# Control_Board_V2.net
KiCad netlist of a schematic drawn in EAGLE
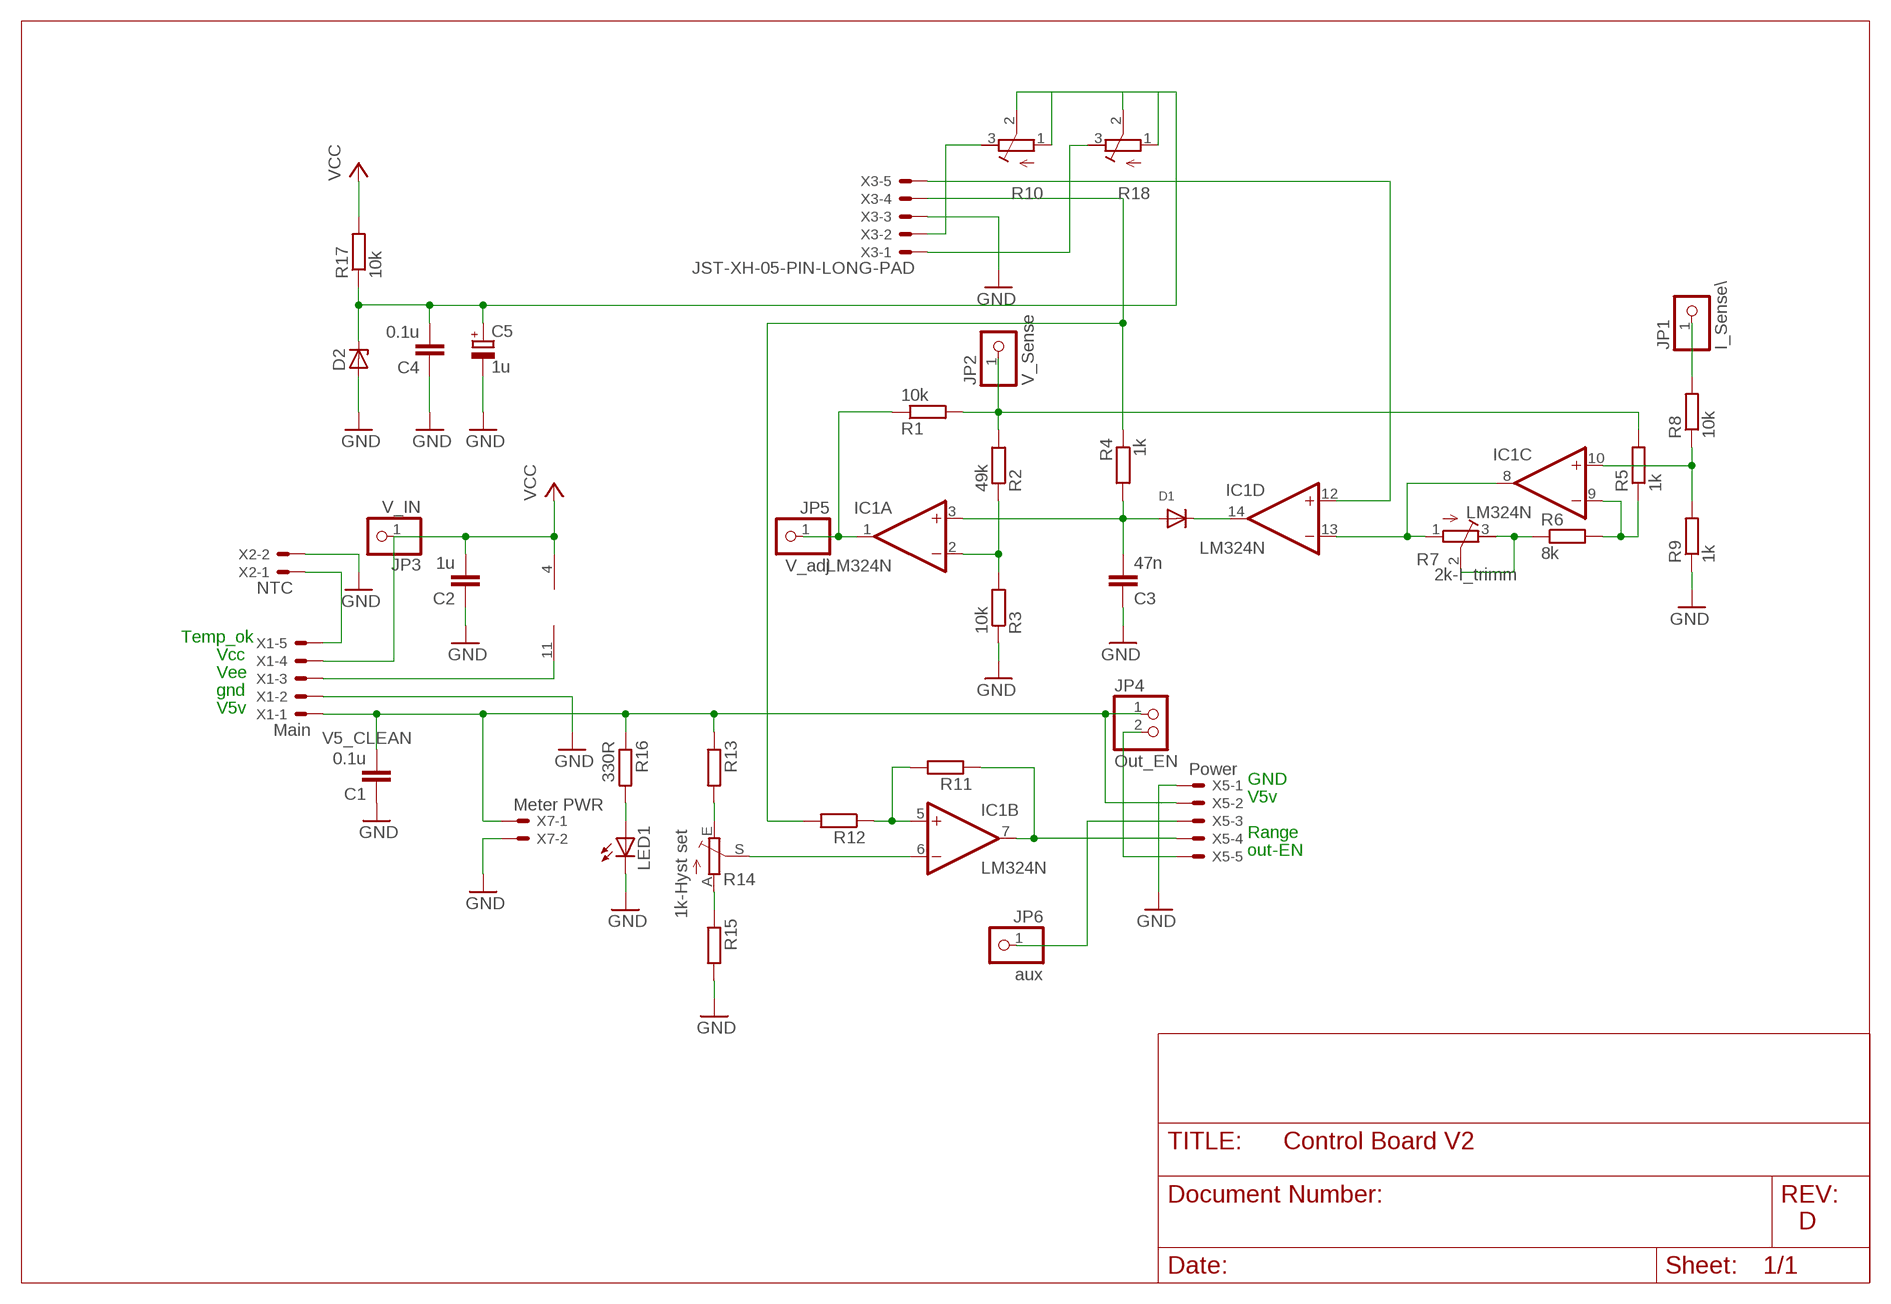
[diagram p0: schematic, sheet 1]

(export (version "E")
  (design (tool "Eeschema 10.0.6"))
  (components
    (comp (ref "C1")
      (value "0.1u")
      (footprint "eagle-import:C050-025X075")
      (libsource (lib "eagle-import") (part "C-EU050-025X075"))
    )
    (comp (ref "C2")
      (value "1u")
      (footprint "eagle-import:C050-025X075")
      (libsource (lib "eagle-import") (part "C-EU050-025X075"))
    )
    (comp (ref "C3")
      (value "47n")
      (footprint "eagle-import:C050-025X075")
      (libsource (lib "eagle-import") (part "C-EU050-025X075"))
    )
    (comp (ref "C4")
      (value "0.1u")
      (footprint "eagle-import:C050-025X075")
      (libsource (lib "eagle-import") (part "C-EU050-025X075"))
    )
    (comp (ref "C5")
      (value "1u")
      (footprint "eagle-import:E5-10,5")
      (libsource (lib "eagle-import") (part "CPOL-EUE5-10.5"))
    )
    (comp (ref "D1")
      (value "DIODEDO-1N4148")
      (footprint "eagle-import:DO-1N4148")
      (libsource (lib "eagle-import") (part "DIODEDO-1N4148"))
    )
    (comp (ref "D2")
      (value "ZENER-DIODEDO35Z10")
      (footprint "eagle-import:DO35Z10")
      (libsource (lib "eagle-import") (part "ZENER-DIODEDO35Z10"))
    )
    (comp (ref "IC1")
      (value "LM324N")
      (footprint "eagle-import:DIL14")
      (libsource (lib "eagle-import") (part "LM324N"))
    )
    (comp (ref "JP1")
      (value "I_Sense\\")
      (footprint "eagle-import:1X01")
      (libsource (lib "eagle-import") (part "PINHD-1X1"))
    )
    (comp (ref "JP2")
      (value "V_Sense")
      (footprint "eagle-import:1X01")
      (libsource (lib "eagle-import") (part "PINHD-1X1"))
    )
    (comp (ref "JP3")
      (value "V_IN")
      (footprint "eagle-import:1X01")
      (libsource (lib "eagle-import") (part "PINHD-1X1"))
    )
    (comp (ref "JP4")
      (value "Out_EN")
      (footprint "eagle-import:1X02")
      (libsource (lib "eagle-import") (part "PINHD-1X2"))
    )
    (comp (ref "JP5")
      (value "V_adj")
      (footprint "eagle-import:1X01")
      (libsource (lib "eagle-import") (part "PINHD-1X1"))
    )
    (comp (ref "JP6")
      (value "aux")
      (footprint "eagle-import:1X01")
      (libsource (lib "eagle-import") (part "PINHD-1X1"))
    )
    (comp (ref "LED1")
      (value "LED3MM")
      (footprint "eagle-import:LED3MM")
      (libsource (lib "eagle-import") (part "LED3MM"))
    )
    (comp (ref "R1")
      (value "10k")
      (footprint "eagle-import:0204_7")
      (libsource (lib "eagle-import") (part "R-EU_0204/7"))
    )
    (comp (ref "R2")
      (value "49k")
      (footprint "eagle-import:0204_7")
      (libsource (lib "eagle-import") (part "R-EU_0204/7"))
    )
    (comp (ref "R3")
      (value "10k")
      (footprint "eagle-import:0204_7")
      (libsource (lib "eagle-import") (part "R-EU_0204/7"))
    )
    (comp (ref "R4")
      (value "1k")
      (footprint "eagle-import:0204_7")
      (libsource (lib "eagle-import") (part "R-EU_0204/7"))
    )
    (comp (ref "R5")
      (value "1k")
      (footprint "eagle-import:0204_5")
      (libsource (lib "eagle-import") (part "R-EU_0204/5"))
    )
    (comp (ref "R6")
      (value "8k")
      (footprint "eagle-import:0204V")
      (libsource (lib "eagle-import") (part "R-EU_0204/2V"))
    )
    (comp (ref "R7")
      (value "2k-I_trimm")
      (footprint "eagle-import:RTRIM64W")
      (libsource (lib "eagle-import") (part "R-TRIMM64W"))
    )
    (comp (ref "R8")
      (value "10k")
      (footprint "eagle-import:0204_7")
      (libsource (lib "eagle-import") (part "R-EU_0204/7"))
    )
    (comp (ref "R9")
      (value "1k")
      (footprint "eagle-import:0204_7")
      (libsource (lib "eagle-import") (part "R-EU_0204/7"))
    )
    (comp (ref "R10")
      (value "R-TRIMM64W")
      (footprint "eagle-import:RTRIM64W")
      (libsource (lib "eagle-import") (part "R-TRIMM64W"))
    )
    (comp (ref "R11")
      (value "R-EU_0204/5")
      (footprint "eagle-import:0204_5")
      (libsource (lib "eagle-import") (part "R-EU_0204/5"))
    )
    (comp (ref "R12")
      (value "R-EU_0204/2V")
      (footprint "eagle-import:0204V")
      (libsource (lib "eagle-import") (part "R-EU_0204/2V"))
    )
    (comp (ref "R13")
      (value "R-EU_0204/2V")
      (footprint "eagle-import:0204V")
      (libsource (lib "eagle-import") (part "R-EU_0204/2V"))
    )
    (comp (ref "R14")
      (value "1k-Hyst set")
      (footprint "eagle-import:B25P")
      (libsource (lib "eagle-import") (part "TRIM_EU-B25P"))
    )
    (comp (ref "R15")
      (value "R-EU_0204/7")
      (footprint "eagle-import:0204_7")
      (libsource (lib "eagle-import") (part "R-EU_0204/7"))
    )
    (comp (ref "R16")
      (value "330R")
      (footprint "eagle-import:0207_2V")
      (libsource (lib "eagle-import") (part "resistor_R-EU_0207/2V"))
    )
    (comp (ref "R17")
      (value "10k")
      (footprint "eagle-import:0204_7")
      (libsource (lib "eagle-import") (part "R-EU_0204/7"))
    )
    (comp (ref "R18")
      (value "R-TRIMM64W")
      (footprint "eagle-import:RTRIM64W")
      (libsource (lib "eagle-import") (part "R-TRIMM64W"))
    )
    (comp (ref "X1")
      (value "Main")
      (footprint "eagle-import:JST-XH-05-PACKAGE-LONG-PAD")
      (libsource (lib "eagle-import") (part "JST-XH-05-PIN-LONG-PAD"))
    )
    (comp (ref "X2")
      (value "NTC")
      (footprint "eagle-import:JST-XH-02-PACKAGE-LONG-PAD")
      (libsource (lib "eagle-import") (part "JST-XH-02-PIN-LONG-PAD"))
    )
    (comp (ref "X3")
      (value "JST-XH-05-PIN-LONG-PAD")
      (footprint "eagle-import:JST-XH-05-PACKAGE-LONG-PAD")
      (libsource (lib "eagle-import") (part "JST-XH-05-PIN-LONG-PAD"))
    )
    (comp (ref "X5")
      (value "Power")
      (footprint "eagle-import:JST-XH-05-PACKAGE-LONG-PAD")
      (libsource (lib "eagle-import") (part "JST-XH-05-PIN-LONG-PAD"))
    )
    (comp (ref "X7")
      (value "Meter PWR")
      (footprint "eagle-import:JST-XH-02-PACKAGE-LONG-PAD")
      (libsource (lib "eagle-import") (part "JST-XH-02-PIN-LONG-PAD"))
    )
  )
  (nets
    (net (code "1") (name "/V5_CLEAN") (class "Default")
      (node (ref "C1") (pin "2") (pinfunction "2_2") (pintype "passive"))
      (node (ref "JP4") (pin "1") (pinfunction "1_1") (pintype "passive"))
      (node (ref "R13") (pin "1") (pinfunction "1_1") (pintype "passive"))
      (node (ref "R16") (pin "1") (pinfunction "1_1") (pintype "passive"))
      (node (ref "X1") (pin "1") (pinfunction "S_1") (pintype "passive"))
      (node (ref "X5") (pin "2") (pinfunction "S_2") (pintype "passive"))
      (node (ref "X7") (pin "1") (pinfunction "S_1") (pintype "passive"))
    )
    (net (code "2") (name "GND") (class "Default")
      (node (ref "C1") (pin "1") (pinfunction "1_1") (pintype "passive"))
      (node (ref "C2") (pin "1") (pinfunction "1_1") (pintype "passive"))
      (node (ref "C3") (pin "1") (pinfunction "1_1") (pintype "passive"))
      (node (ref "C4") (pin "1") (pinfunction "1_1") (pintype "passive"))
      (node (ref "C5") (pin "-") (pinfunction "-_-") (pintype "passive"))
      (node (ref "D2") (pin "A") (pinfunction "A_A") (pintype "passive"))
      (node (ref "LED1") (pin "K") (pinfunction "C_K") (pintype "passive"))
      (node (ref "R15") (pin "2") (pinfunction "2_2") (pintype "passive"))
      (node (ref "R3") (pin "1") (pinfunction "1_1") (pintype "passive"))
      (node (ref "R9") (pin "1") (pinfunction "1_1") (pintype "passive"))
      (node (ref "X1") (pin "2") (pinfunction "S_2") (pintype "passive"))
      (node (ref "X2") (pin "2") (pinfunction "S_2") (pintype "passive"))
      (node (ref "X3") (pin "3") (pinfunction "S_3") (pintype "passive"))
      (node (ref "X5") (pin "1") (pinfunction "S_1") (pintype "passive"))
      (node (ref "X7") (pin "2") (pinfunction "S_2") (pintype "passive"))
    )
    (net (code "3") (name "Net-(IC1A-+IN)") (class "Default")
      (node (ref "C3") (pin "2") (pinfunction "2_2") (pintype "passive"))
      (node (ref "D1") (pin "A") (pinfunction "A_A") (pintype "passive"))
      (node (ref "IC1") (pin "3") (pinfunction "+IN_3") (pintype "input"))
      (node (ref "R4") (pin "2") (pinfunction "2_2") (pintype "passive"))
    )
    (net (code "4") (name "Net-(IC1A--IN)") (class "Default")
      (node (ref "IC1") (pin "2") (pinfunction "-IN_2") (pintype "input"))
      (node (ref "R2") (pin "1") (pinfunction "1_1") (pintype "passive"))
      (node (ref "R3") (pin "2") (pinfunction "2_2") (pintype "passive"))
    )
    (net (code "5") (name "Net-(IC1A-OUT)") (class "Default")
      (node (ref "IC1") (pin "1") (pinfunction "OUT_1") (pintype "output"))
      (node (ref "JP5") (pin "1") (pinfunction "1_1") (pintype "passive"))
      (node (ref "R1") (pin "1") (pinfunction "1_1") (pintype "passive"))
    )
    (net (code "6") (name "Net-(IC1B-+IN)") (class "Default")
      (node (ref "IC1") (pin "5") (pinfunction "+IN_5") (pintype "input"))
      (node (ref "R11") (pin "2") (pinfunction "2_2") (pintype "passive"))
      (node (ref "R12") (pin "1") (pinfunction "1_1") (pintype "passive"))
    )
    (net (code "7") (name "Net-(IC1B--IN)") (class "Default")
      (node (ref "IC1") (pin "6") (pinfunction "-IN_6") (pintype "input"))
      (node (ref "R14") (pin "S") (pinfunction "S_S") (pintype "passive"))
    )
    (net (code "8") (name "Net-(IC1B-OUT)") (class "Default")
      (node (ref "IC1") (pin "7") (pinfunction "OUT_7") (pintype "output"))
      (node (ref "R11") (pin "1") (pinfunction "1_1") (pintype "passive"))
      (node (ref "X5") (pin "4") (pinfunction "S_4") (pintype "passive"))
    )
    (net (code "9") (name "Net-(IC1C-+IN)") (class "Default")
      (node (ref "IC1") (pin "10") (pinfunction "+IN_10") (pintype "input"))
      (node (ref "R8") (pin "1") (pinfunction "1_1") (pintype "passive"))
      (node (ref "R9") (pin "2") (pinfunction "2_2") (pintype "passive"))
    )
    (net (code "10") (name "Net-(IC1C--IN)") (class "Default")
      (node (ref "IC1") (pin "9") (pinfunction "-IN_9") (pintype "input"))
      (node (ref "R5") (pin "1") (pinfunction "1_1") (pintype "passive"))
      (node (ref "R6") (pin "2") (pinfunction "2_2") (pintype "passive"))
    )
    (net (code "11") (name "Net-(IC1C-OUT)") (class "Default")
      (node (ref "IC1") (pin "13") (pinfunction "-IN_13") (pintype "input"))
      (node (ref "IC1") (pin "8") (pinfunction "OUT_8") (pintype "output"))
      (node (ref "R7") (pin "1") (pinfunction "A_1") (pintype "passive"))
    )
    (net (code "12") (name "Net-(IC1D-+IN)") (class "Default")
      (node (ref "IC1") (pin "12") (pinfunction "+IN_12") (pintype "input"))
      (node (ref "X3") (pin "5") (pinfunction "S_5") (pintype "passive"))
    )
    (net (code "13") (name "Net-(IC1D-OUT)") (class "Default")
      (node (ref "D1") (pin "C") (pinfunction "C_C") (pintype "passive"))
      (node (ref "IC1") (pin "14") (pinfunction "OUT_14") (pintype "output"))
    )
    (net (code "14") (name "Net-(IC1E-V-)") (class "Default")
      (node (ref "IC1") (pin "11") (pinfunction "V-_11") (pintype "power_in"))
      (node (ref "X1") (pin "3") (pinfunction "S_3") (pintype "passive"))
    )
    (net (code "15") (name "Net-(JP1-Pad1)") (class "Default")
      (node (ref "JP1") (pin "1") (pinfunction "1_1") (pintype "passive"))
      (node (ref "R8") (pin "2") (pinfunction "2_2") (pintype "passive"))
    )
    (net (code "16") (name "Net-(JP2-Pad1)") (class "Default")
      (node (ref "JP2") (pin "1") (pinfunction "1_1") (pintype "passive"))
      (node (ref "R1") (pin "2") (pinfunction "2_2") (pintype "passive"))
      (node (ref "R2") (pin "2") (pinfunction "2_2") (pintype "passive"))
      (node (ref "R5") (pin "2") (pinfunction "2_2") (pintype "passive"))
    )
    (net (code "17") (name "Net-(LED1-PadA)") (class "Default")
      (node (ref "LED1") (pin "A") (pinfunction "A_A") (pintype "passive"))
      (node (ref "R16") (pin "2") (pinfunction "2_2") (pintype "passive"))
    )
    (net (code "18") (name "Net-(R7-E)") (class "Default")
      (node (ref "R6") (pin "1") (pinfunction "1_1") (pintype "passive"))
      (node (ref "R7") (pin "2") (pinfunction "S_2") (pintype "passive"))
      (node (ref "R7") (pin "3") (pinfunction "E_3") (pintype "passive"))
    )
    (net (code "19") (name "Net-(R10-A)") (class "Default")
      (node (ref "C4") (pin "2") (pinfunction "2_2") (pintype "passive"))
      (node (ref "C5") (pin "+") (pinfunction "+_+") (pintype "passive"))
      (node (ref "D2") (pin "C") (pinfunction "C_C") (pintype "passive"))
      (node (ref "R10") (pin "1") (pinfunction "A_1") (pintype "passive"))
      (node (ref "R10") (pin "2") (pinfunction "S_2") (pintype "passive"))
      (node (ref "R17") (pin "1") (pinfunction "1_1") (pintype "passive"))
      (node (ref "R18") (pin "1") (pinfunction "A_1") (pintype "passive"))
      (node (ref "R18") (pin "2") (pinfunction "S_2") (pintype "passive"))
    )
    (net (code "20") (name "Net-(R10-E)") (class "Default")
      (node (ref "R10") (pin "3") (pinfunction "E_3") (pintype "passive"))
      (node (ref "X3") (pin "2") (pinfunction "S_2") (pintype "passive"))
    )
    (net (code "21") (name "Net-(R13-Pad2)") (class "Default")
      (node (ref "R13") (pin "2") (pinfunction "2_2") (pintype "passive"))
      (node (ref "R14") (pin "E") (pinfunction "E_E") (pintype "passive"))
    )
    (net (code "22") (name "Net-(R14-PadA)") (class "Default")
      (node (ref "R14") (pin "A") (pinfunction "A_A") (pintype "passive"))
      (node (ref "R15") (pin "1") (pinfunction "1_1") (pintype "passive"))
    )
    (net (code "23") (name "Net-(R18-E)") (class "Default")
      (node (ref "R18") (pin "3") (pinfunction "E_3") (pintype "passive"))
      (node (ref "X3") (pin "1") (pinfunction "S_1") (pintype "passive"))
    )
    (net (code "24") (name "Net-(X1E-S)") (class "Default")
      (node (ref "X1") (pin "5") (pinfunction "S_5") (pintype "passive"))
      (node (ref "X2") (pin "1") (pinfunction "S_1") (pintype "passive"))
    )
    (net (code "25") (name "Net-(X3D-S)") (class "Default")
      (node (ref "R12") (pin "2") (pinfunction "2_2") (pintype "passive"))
      (node (ref "R4") (pin "1") (pinfunction "1_1") (pintype "passive"))
      (node (ref "X3") (pin "4") (pinfunction "S_4") (pintype "passive"))
    )
    (net (code "26") (name "Net-(X5C-S)") (class "Default")
      (node (ref "JP6") (pin "1") (pinfunction "1_1") (pintype "passive"))
      (node (ref "X5") (pin "3") (pinfunction "S_3") (pintype "passive"))
    )
    (net (code "27") (name "Net-(X5E-S)") (class "Default")
      (node (ref "JP4") (pin "2") (pinfunction "2_2") (pintype "passive"))
      (node (ref "X5") (pin "5") (pinfunction "S_5") (pintype "passive"))
    )
    (net (code "28") (name "VCC") (class "Default")
      (node (ref "C2") (pin "2") (pinfunction "2_2") (pintype "passive"))
      (node (ref "IC1") (pin "4") (pinfunction "V+_4") (pintype "power_in"))
      (node (ref "JP3") (pin "1") (pinfunction "1_1") (pintype "passive"))
      (node (ref "R17") (pin "2") (pinfunction "2_2") (pintype "passive"))
      (node (ref "X1") (pin "4") (pinfunction "S_4") (pintype "passive"))
    )
  )
)
